# Transmitters.net
KiCad netlist of a schematic drawn in Altium Designer
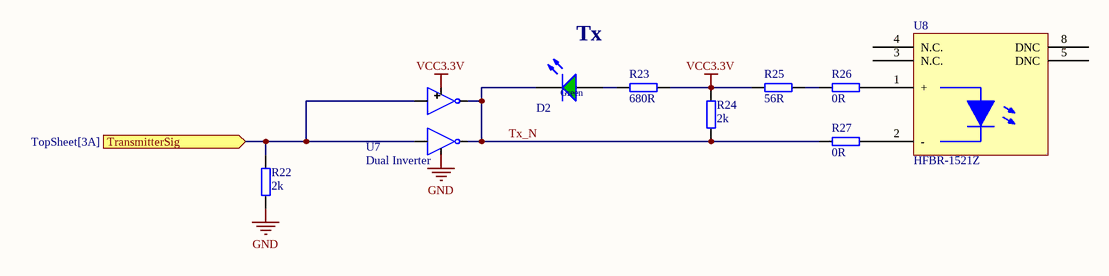
[diagram p0: Transmitters.SchDoc]

(export (version "E")
  (design (tool "Eeschema 10.0.6"))
  (components
    (comp (ref "D2")
      (value "150060GS75000")
      (footprint "WL-SMCW_0603")
      (description "WL-SMCW SMD Mono-color Chip LED Waterclear, size 0603, Green, 3.2 V, 140°")
      (fields
        (field (name "MF") "Wuerth Elektronik")
        (field (name "LCSC PART #") "C72043")
        (field (name "CREATED") "2018_09_06_AGeiger")
      )
      (libsource (lib "UZOhm_Optical") (part "LED_Green_0603"))
    )
    (comp (ref "R22")
      (value "2k")
      (footprint "R_0603_N")
      (description "SMD Resistor 0603")
      (fields
        (field (name "TOLERANCE") "1%")
        (field (name "VOLTAGE") "75 V")
        (field (name "CREATED") "2018_09_06_AGeiger")
      )
      (libsource (lib "UZOhm_Optical") (part "R_0603"))
    )
    (comp (ref "R23")
      (value "680R")
      (footprint "R_0603_N")
      (description "SMD Resistor 0603")
      (fields
        (field (name "TOLERANCE") "1%")
        (field (name "VOLTAGE") "75V")
        (field (name "CREATED") "2018_09_06_AGeiger")
      )
      (libsource (lib "UZOhm_Optical") (part "R_0603"))
    )
    (comp (ref "R24")
      (value "2k")
      (footprint "R_0603_N")
      (description "SMD Resistor 0603")
      (fields
        (field (name "TOLERANCE") "1%")
        (field (name "VOLTAGE") "75 V")
        (field (name "CREATED") "2018_09_06_AGeiger")
      )
      (libsource (lib "UZOhm_Optical") (part "R_0603"))
    )
    (comp (ref "R25")
      (value "56R")
      (footprint "RES_2012X06N")
      (description "SMD Resistor 0805")
      (fields (field (name "MF") "Bourns") (field (name "MPN") "CR0805-FX-1200ELF"))
      (libsource (lib "UZOhm_Optical") (part "R_0805"))
    )
    (comp (ref "R26")
      (value "0R")
      (footprint "R_0603_N")
      (description "SMD Resistor 0603")
      (fields
        (field (name "TOLERANCE") "1%")
        (field (name "VOLTAGE") "75V")
        (field (name "CREATED") "2018_09_06_AGeiger")
      )
      (libsource (lib "UZOhm_Optical") (part "R_0603_JLC"))
    )
    (comp (ref "R27")
      (value "0R")
      (footprint "R_0603_N")
      (description "SMD Resistor 0603")
      (fields
        (field (name "TOLERANCE") "1%")
        (field (name "VOLTAGE") "75V")
        (field (name "CREATED") "2018_09_06_AGeiger")
      )
      (libsource (lib "UZOhm_Optical") (part "R_0603_JLC"))
    )
    (comp (ref "U7")
      (value "Dual Inverter")
      (footprint "SN74LVC2GU04DCKR")
      (description "This dual inverter is designed for 1.65-V to 5.5-V VCC\r\noperation.")
      (fields (field (name "LCSC PART #") "C116660"))
      (libsource (lib "UZOhm_Optical") (part "SN74LVC2GU04DCKR"))
    )
    (comp (ref "U8")
      (value "HFBR-1521Z")
      (footprint "HFBRx5XX")
      (description "Fibre Optic Transmitters, Link Horiz 5MBd Tx RoHS")
      (fields (field (name "MF") "Broadcom/Avago") (field (name "CREATED") "2019_04_09_Kreppel"))
      (libsource (lib "HLU TUM") (part "HFBR-1521Z"))
    )
  )
  (nets
    (net (code "1") (name "/TransmitterSig") (class "Default")
      (node (ref "R22") (pin "2") (pinfunction "2_2") (pintype "passive"))
      (node (ref "U7") (pin "1") (pinfunction "IN1_1") (pintype "passive"))
      (node (ref "U7") (pin "3") (pinfunction "IN2_3") (pintype "passive"))
    )
    (net (code "2") (name "/Tx_N") (class "Default")
      (node (ref "D2") (pin "1") (pinfunction "K_1") (pintype "passive"))
      (node (ref "R24") (pin "1") (pinfunction "1_1") (pintype "passive"))
      (node (ref "R27") (pin "1") (pinfunction "1_1") (pintype "passive"))
      (node (ref "U7") (pin "4") (pinfunction "OUT2_4") (pintype "passive"))
      (node (ref "U7") (pin "6") (pinfunction "OUT2_6") (pintype "passive"))
    )
    (net (code "3") (name "GND") (class "Default")
      (node (ref "R22") (pin "1") (pinfunction "1_1") (pintype "passive"))
      (node (ref "U7") (pin "2") (pinfunction "GND_2") (pintype "passive"))
    )
    (net (code "4") (name "Net-(D2-A)") (class "Default")
      (node (ref "D2") (pin "2") (pinfunction "A_2") (pintype "passive"))
      (node (ref "R23") (pin "2") (pinfunction "2_2") (pintype "passive"))
    )
    (net (code "5") (name "Net-(R25-Pad2)") (class "Default")
      (node (ref "R25") (pin "2") (pintype "passive"))
      (node (ref "R26") (pin "1") (pinfunction "1_1") (pintype "passive"))
    )
    (net (code "6") (name "Net-(U8-+)") (class "Default")
      (node (ref "R26") (pin "2") (pinfunction "2_2") (pintype "passive"))
      (node (ref "U8") (pin "1") (pinfunction "+_1") (pintype "passive"))
    )
    (net (code "7") (name "Net-(U8--)") (class "Default")
      (node (ref "R27") (pin "2") (pinfunction "2_2") (pintype "passive"))
      (node (ref "U8") (pin "2") (pinfunction "-_2") (pintype "passive"))
    )
    (net (code "8") (name "VCC3.3V") (class "Default")
      (node (ref "R23") (pin "1") (pinfunction "1_1") (pintype "passive"))
      (node (ref "R24") (pin "2") (pinfunction "2_2") (pintype "passive"))
      (node (ref "R25") (pin "1") (pintype "passive"))
      (node (ref "U7") (pin "5") (pinfunction "VCC_5") (pintype "passive"))
    )
    (net (code "9") (name "unconnected-(U8-DNC-Pad5)") (class "Default")
      (node (ref "U8") (pin "5") (pinfunction "DNC_5") (pintype "passive"))
    )
    (net (code "10") (name "unconnected-(U8-DNC-Pad8)") (class "Default")
      (node (ref "U8") (pin "8") (pinfunction "DNC_8") (pintype "passive"))
    )
    (net (code "11") (name "unconnected-(U8-N.C.-Pad3)") (class "Default")
      (node (ref "U8") (pin "3") (pinfunction "N.C._3") (pintype "passive"))
    )
    (net (code "12") (name "unconnected-(U8-N.C.-Pad4)") (class "Default")
      (node (ref "U8") (pin "4") (pinfunction "N.C._4") (pintype "passive"))
    )
  )
)
